# Mutli-Stepper-Driver_Rev_2_MRlocal.net
KiCad netlist of a schematic drawn in EAGLE
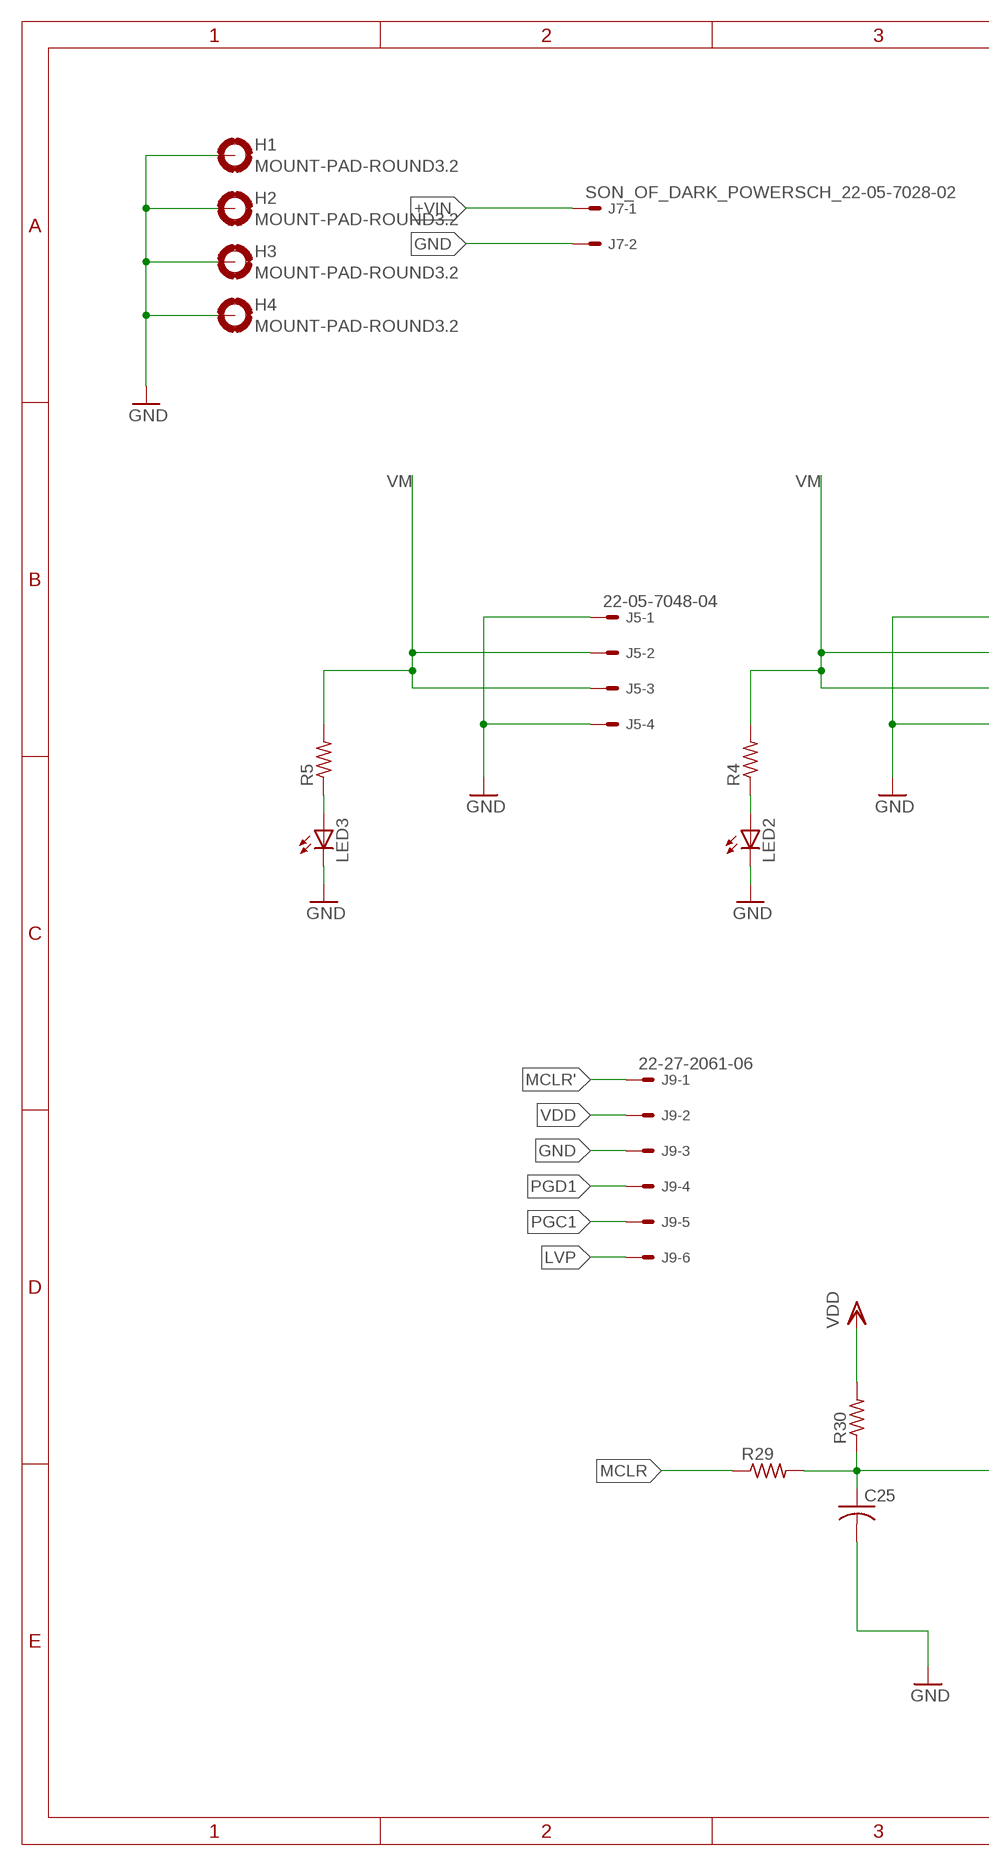
[diagram p0: schematic, sheet 1, part 1 of 2]
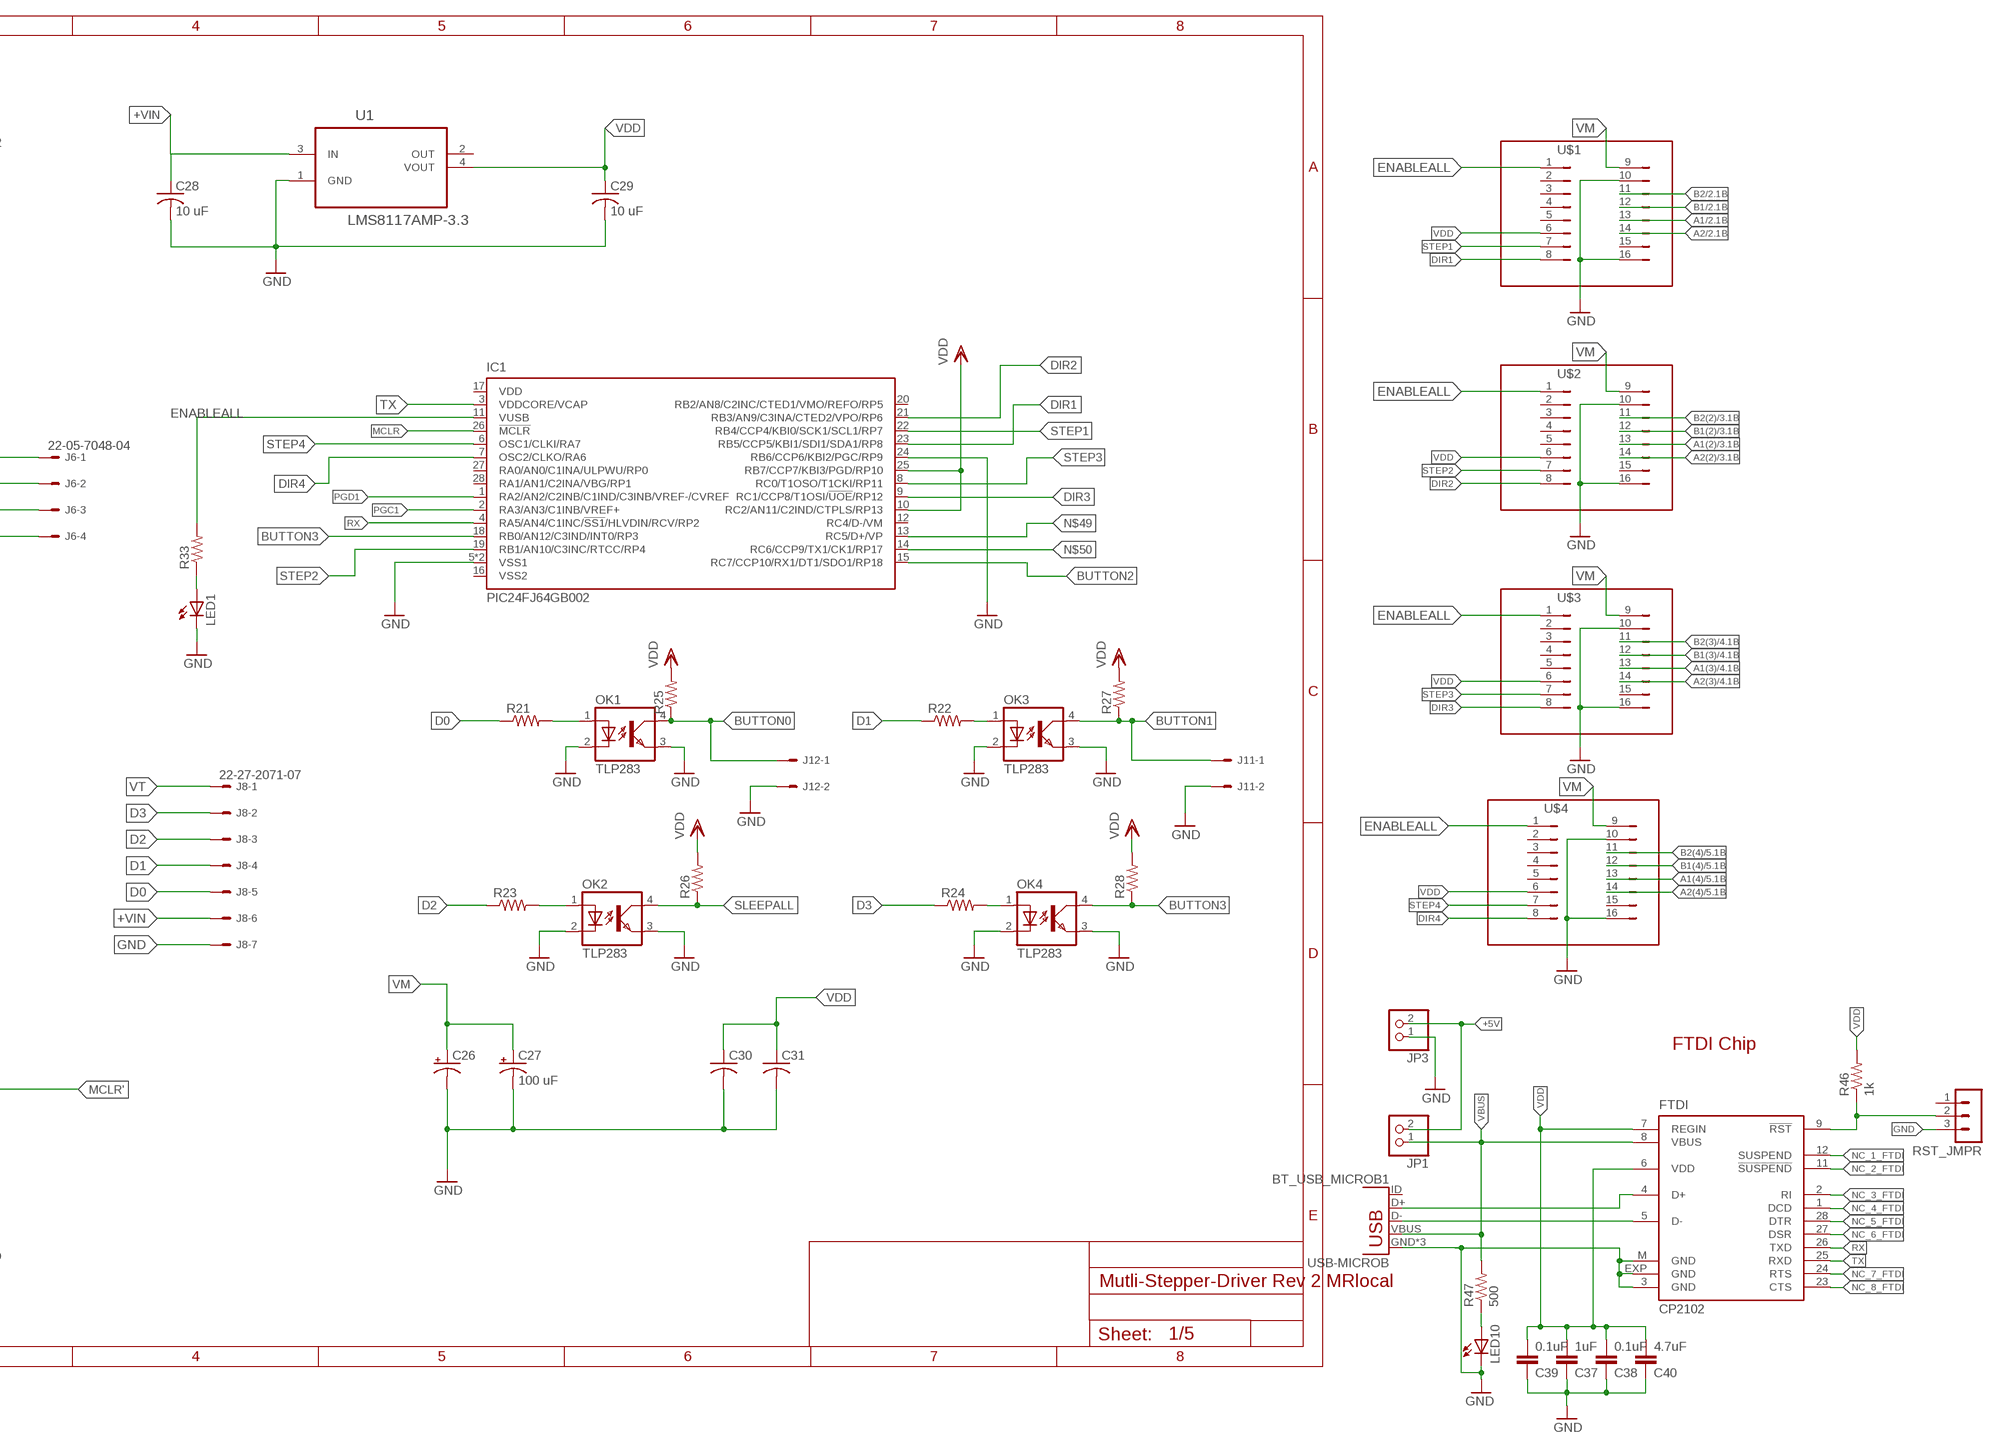
[diagram p1: schematic, sheet 1, part 2 of 2]
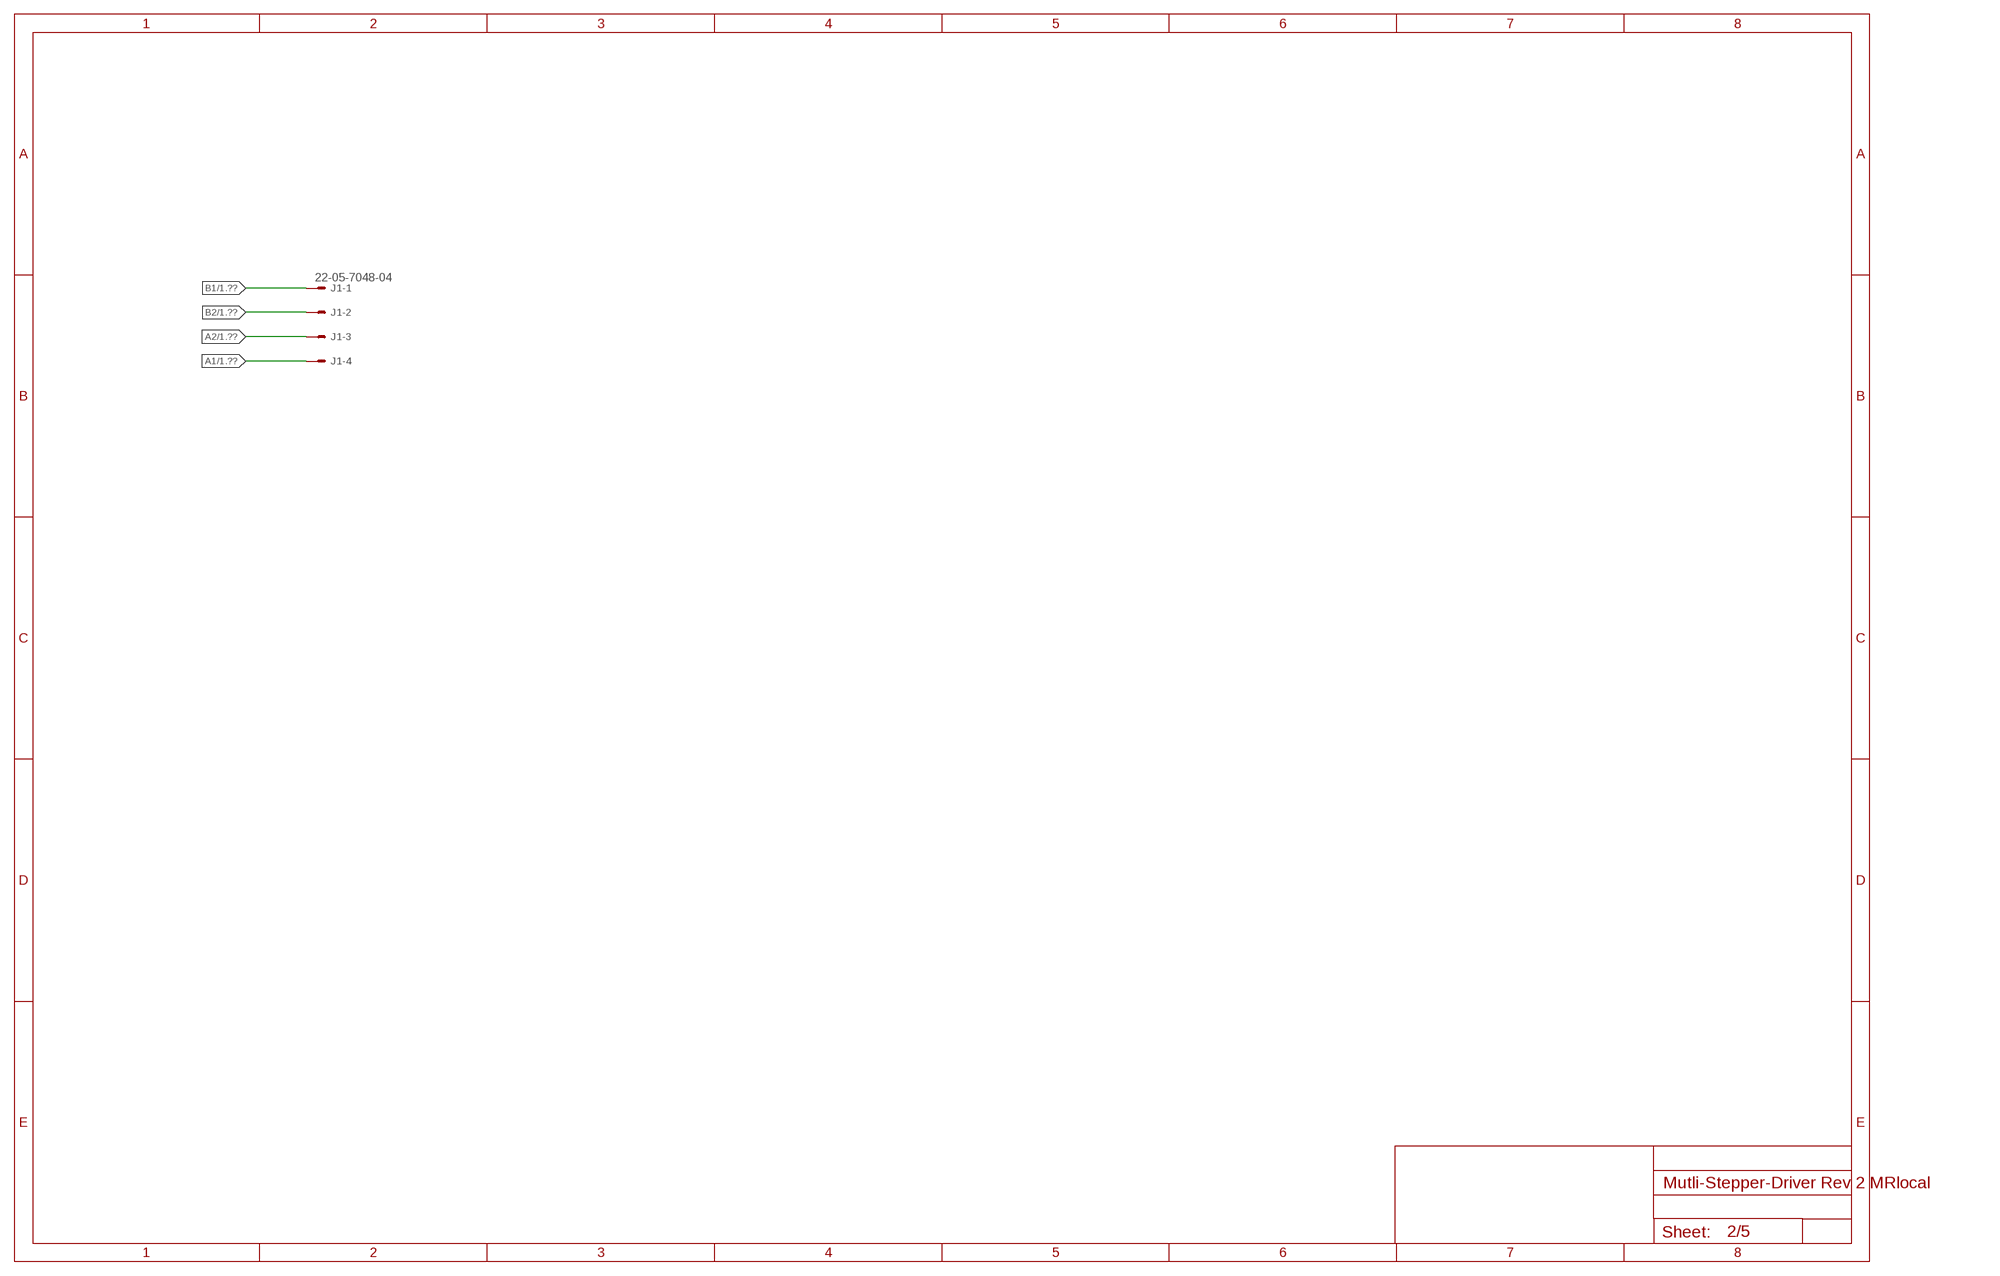
[diagram p2: schematic, sheet 2]
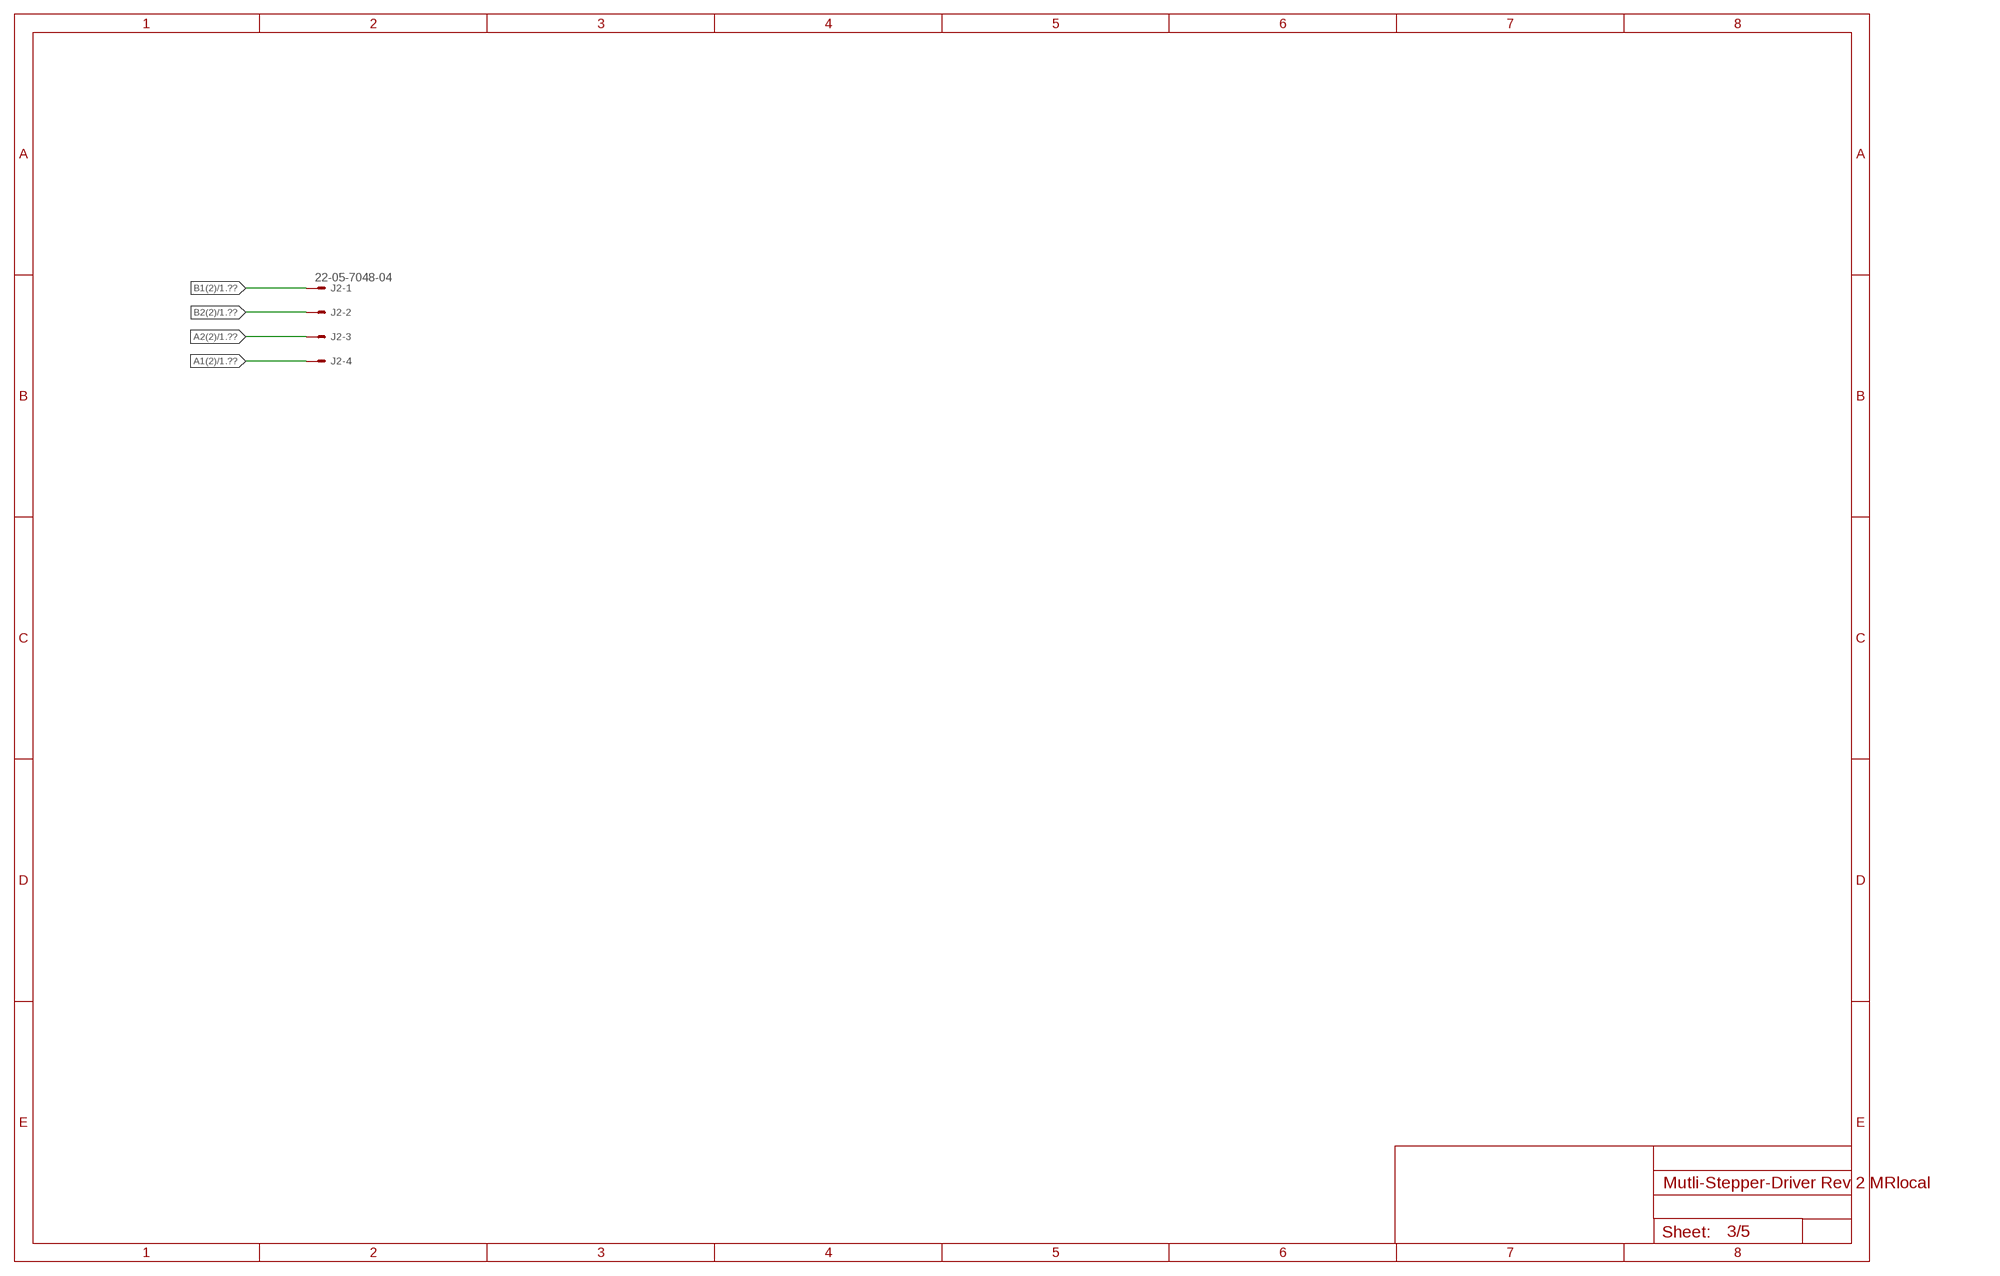
[diagram p3: schematic, sheet 3]
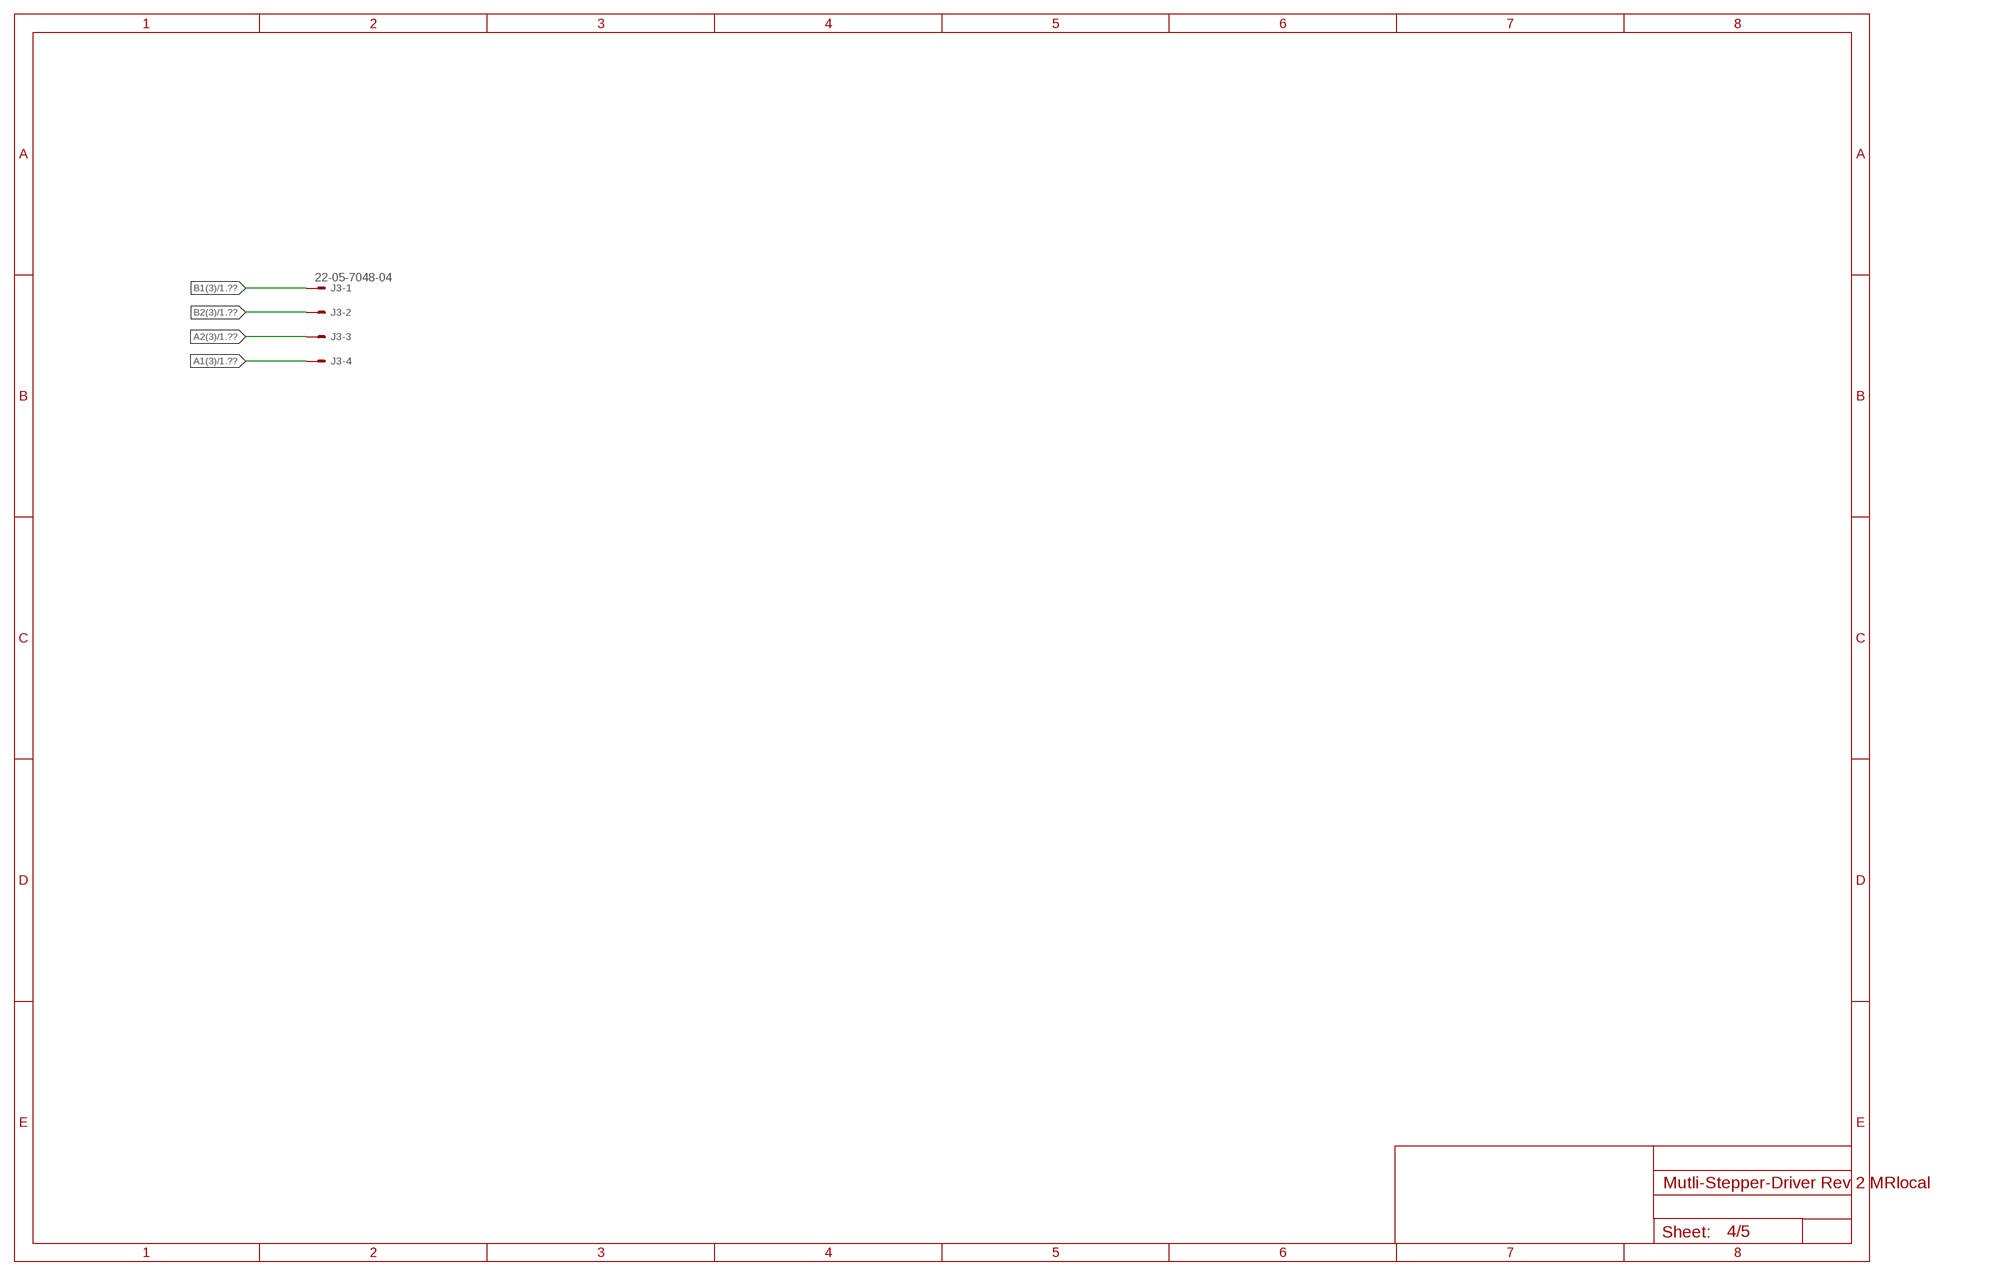
[diagram p4: schematic, sheet 4]
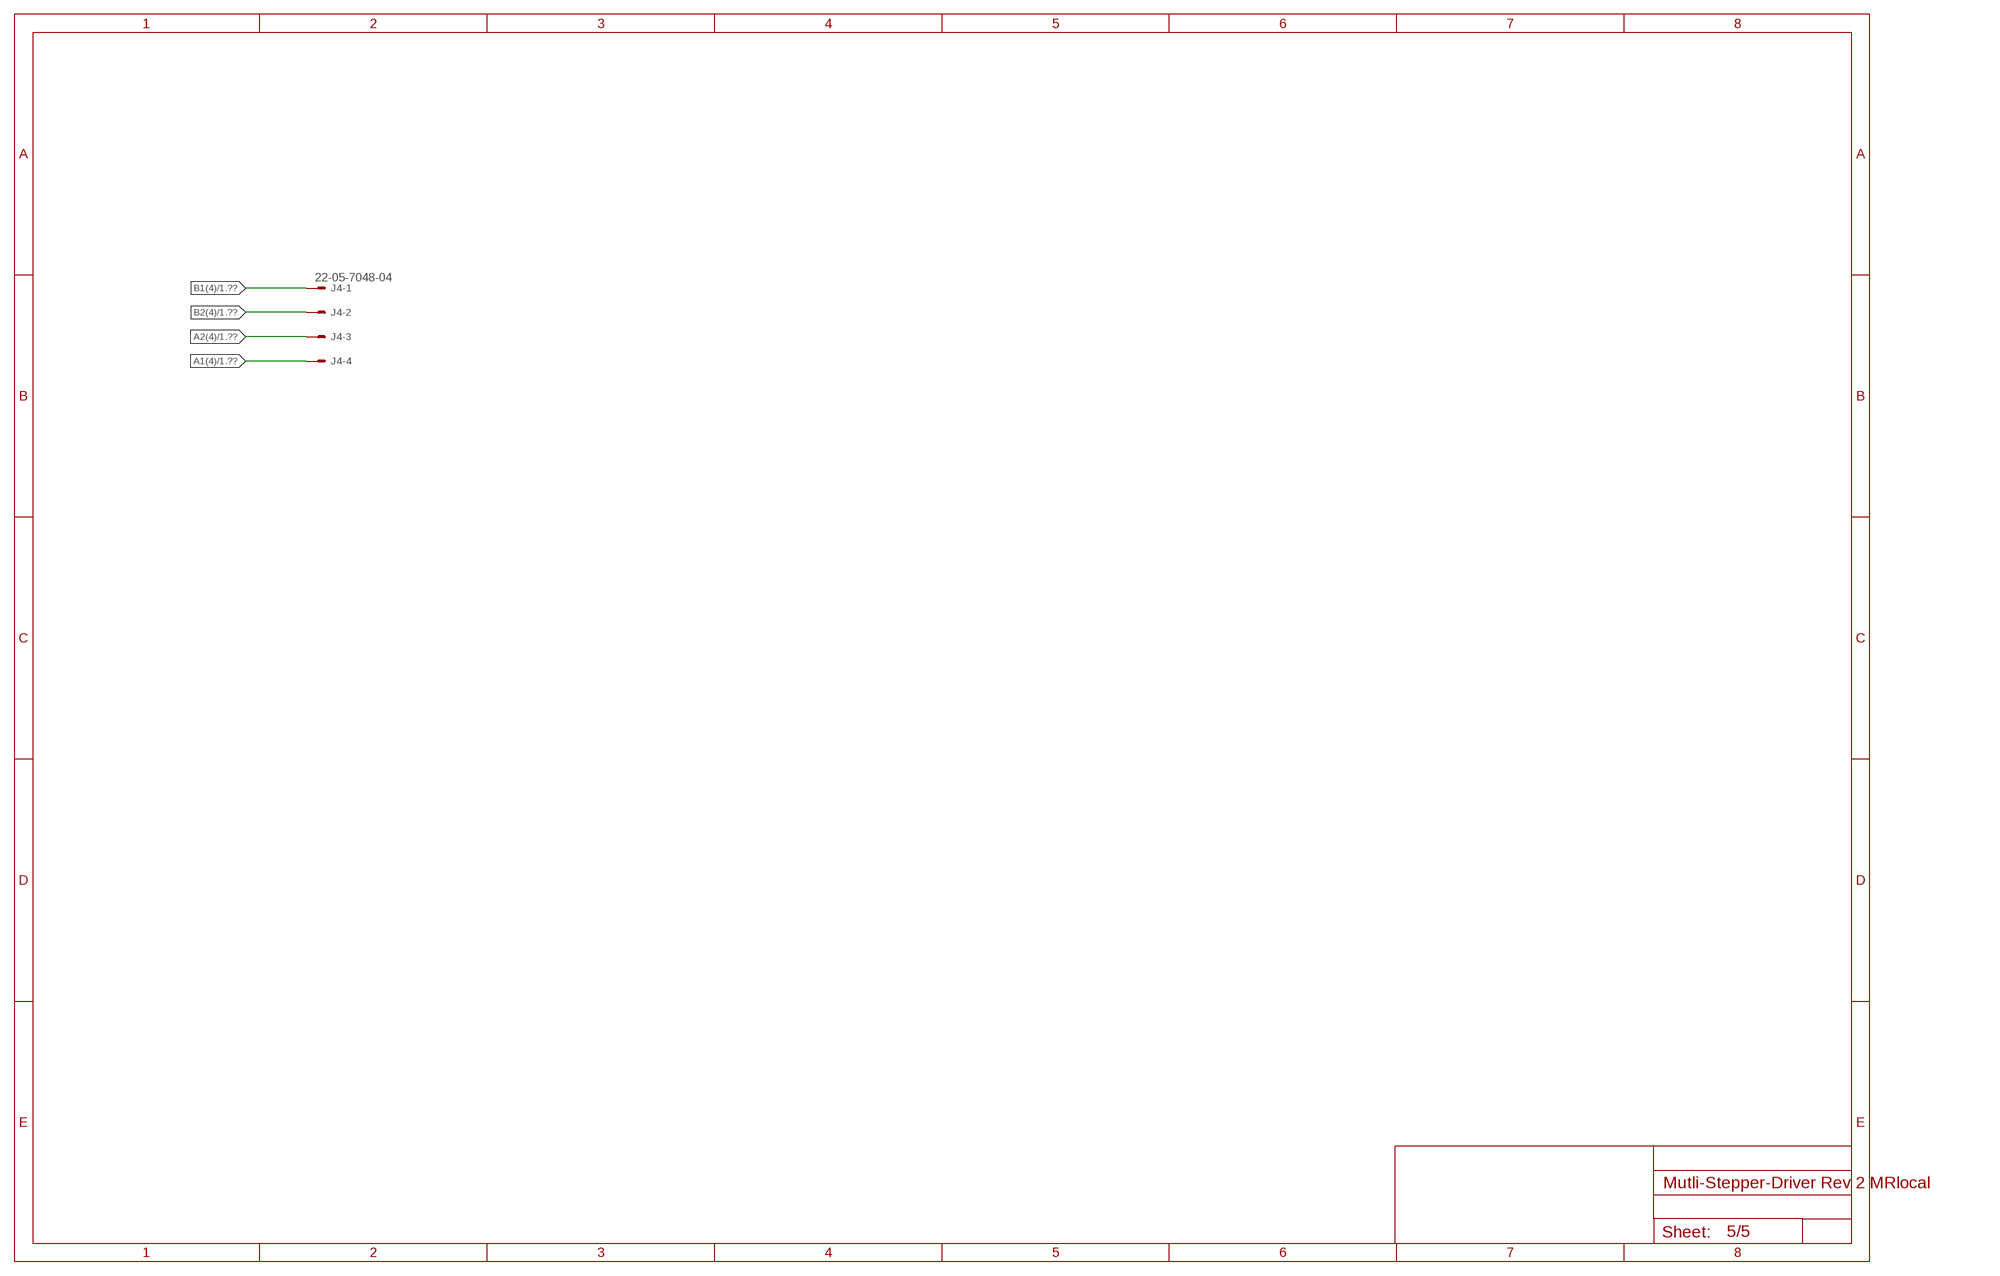
[diagram p5: schematic, sheet 5]

(export (version "E")
  (design (tool "Eeschema 10.0.6"))
  (components
    (comp (ref "J2")
      (value "22-05-7048-04")
      (footprint "eagle-import:7395-04")
      (libsource (lib "eagle-import") (part "22-?-0405-7048"))
    )
    (comp (ref "J3")
      (value "22-05-7048-04")
      (footprint "eagle-import:7395-04")
      (libsource (lib "eagle-import") (part "22-?-0405-7048"))
    )
    (comp (ref "J1")
      (value "22-05-7048-04")
      (footprint "eagle-import:7395-04")
      (libsource (lib "eagle-import") (part "22-?-0405-7048"))
    )
    (comp (ref "BT_USB_MICROB1")
      (value "USB-MICROB")
      (footprint "eagle-import:USB-MICROB")
      (libsource (lib "eagle-import") (part "USB-MICROB"))
    )
    (comp (ref "C25")
      (value "C-USC0805")
      (footprint "eagle-import:C0805")
      (libsource (lib "eagle-import") (part "C-USC0805"))
    )
    (comp (ref "C26")
      (value "CPOL-USCT7343")
      (footprint "eagle-import:CT7343")
      (libsource (lib "eagle-import") (part "CPOL-USCT7343"))
    )
    (comp (ref "C27")
      (value "100 uF")
      (footprint "eagle-import:CT7343")
      (libsource (lib "eagle-import") (part "CPOL-USCT7343"))
    )
    (comp (ref "C28")
      (value "10 uF")
      (footprint "eagle-import:C3216")
      (libsource (lib "eagle-import") (part "C-USC3216"))
    )
    (comp (ref "C29")
      (value "10 uF")
      (footprint "eagle-import:C3216")
      (libsource (lib "eagle-import") (part "C-USC3216"))
    )
    (comp (ref "C30")
      (value "C-USC0805")
      (footprint "eagle-import:C0805")
      (libsource (lib "eagle-import") (part "C-USC0805"))
    )
    (comp (ref "C31")
      (value "C-USC0805")
      (footprint "eagle-import:C0805")
      (libsource (lib "eagle-import") (part "C-USC0805"))
    )
    (comp (ref "C37")
      (value "1uF")
      (footprint "eagle-import:C0805")
      (libsource (lib "eagle-import") (part "C-EUC0805"))
    )
    (comp (ref "C38")
      (value "0.1uF")
      (footprint "eagle-import:C0805")
      (libsource (lib "eagle-import") (part "C-EUC0805"))
    )
    (comp (ref "C39")
      (value "0.1uF")
      (footprint "eagle-import:C0805")
      (libsource (lib "eagle-import") (part "C-EUC0805"))
    )
    (comp (ref "C40")
      (value "4.7uF")
      (footprint "eagle-import:C0805")
      (libsource (lib "eagle-import") (part "C-EUC0805"))
    )
    (comp (ref "FTDI")
      (value "CP2102")
      (footprint "eagle-import:MLP28")
      (fields (field (name "MF") "FARNELL") (field (name "MPN") "CP2102-GM"))
      (libsource (lib "eagle-import") (part "CP2102"))
    )
    (comp (ref "H1")
      (value "MOUNT-PAD-ROUND3.2")
      (footprint "eagle-import:3,2-PAD")
      (libsource (lib "eagle-import") (part "MOUNT-PAD-ROUND3.2"))
    )
    (comp (ref "H2")
      (value "MOUNT-PAD-ROUND3.2")
      (footprint "eagle-import:3,2-PAD")
      (libsource (lib "eagle-import") (part "MOUNT-PAD-ROUND3.2"))
    )
    (comp (ref "H3")
      (value "MOUNT-PAD-ROUND3.2")
      (footprint "eagle-import:3,2-PAD")
      (libsource (lib "eagle-import") (part "MOUNT-PAD-ROUND3.2"))
    )
    (comp (ref "H4")
      (value "MOUNT-PAD-ROUND3.2")
      (footprint "eagle-import:3,2-PAD")
      (libsource (lib "eagle-import") (part "MOUNT-PAD-ROUND3.2"))
    )
    (comp (ref "IC1")
      (value "PIC24FJ64GB002")
      (footprint "eagle-import:MICROCHIP_QFN28-ML_6X6MM")
      (libsource (lib "eagle-import") (part "MICROCHIP_PIC18F2J53ML"))
    )
    (comp (ref "J5")
      (value "22-05-7048-04")
      (footprint "eagle-import:7395-04")
      (libsource (lib "eagle-import") (part "22-?-0405-7048"))
    )
    (comp (ref "J6")
      (value "22-05-7048-04")
      (footprint "eagle-import:7395-04")
      (libsource (lib "eagle-import") (part "22-?-0405-7048"))
    )
    (comp (ref "J7")
      (value "SON_OF_DARK_POWERSCH_22-05-7028-02")
      (footprint "eagle-import:SON_OF_DARK_POWERSCH_7395-02")
      (libsource (lib "eagle-import") (part "SON_OF_DARK_POWERSCH_22-?-0205-7028"))
    )
    (comp (ref "J8")
      (value "22-27-2071-07")
      (footprint "eagle-import:6410-07")
      (libsource (lib "eagle-import") (part "22-?-0727-2071"))
    )
    (comp (ref "J9")
      (value "22-27-2061-06")
      (footprint "eagle-import:6410-06")
      (libsource (lib "eagle-import") (part "22-?-0627-2061"))
    )
    (comp (ref "J11")
      (value "SON_OF_DARK_POWERSCH_22-05-7028-02")
      (footprint "eagle-import:SON_OF_DARK_POWERSCH_7395-02")
      (libsource (lib "eagle-import") (part "SON_OF_DARK_POWERSCH_22-?-0205-7028"))
    )
    (comp (ref "J12")
      (value "SON_OF_DARK_POWERSCH_22-05-7028-02")
      (footprint "eagle-import:SON_OF_DARK_POWERSCH_7395-02")
      (libsource (lib "eagle-import") (part "SON_OF_DARK_POWERSCH_22-?-0205-7028"))
    )
    (comp (ref "JP1")
      (value "PINHD-1X2")
      (footprint "eagle-import:1X02")
      (libsource (lib "eagle-import") (part "PINHD-1X2"))
    )
    (comp (ref "JP3")
      (value "PINHD-1X2")
      (footprint "eagle-import:1X02")
      (libsource (lib "eagle-import") (part "PINHD-1X2"))
    )
    (comp (ref "LED1")
      (value "LEDCHIPLED_0805")
      (footprint "eagle-import:CHIPLED_0805")
      (libsource (lib "eagle-import") (part "led_LEDCHIPLED_0805"))
    )
    (comp (ref "LED2")
      (value "LEDCHIPLED_0805")
      (footprint "eagle-import:CHIPLED_0805")
      (libsource (lib "eagle-import") (part "led_LEDCHIPLED_0805"))
    )
    (comp (ref "LED3")
      (value "LEDCHIPLED_0805")
      (footprint "eagle-import:CHIPLED_0805")
      (libsource (lib "eagle-import") (part "led_LEDCHIPLED_0805"))
    )
    (comp (ref "LED10")
      (value "LEDSML0603")
      (footprint "eagle-import:SML0603")
      (libsource (lib "eagle-import") (part "LEDSML0603"))
    )
    (comp (ref "OK1")
      (value "TLP283")
      (footprint "eagle-import:MINI-FLAT-4")
      (libsource (lib "eagle-import") (part "TLP283"))
    )
    (comp (ref "OK2")
      (value "TLP283")
      (footprint "eagle-import:MINI-FLAT-4")
      (libsource (lib "eagle-import") (part "TLP283"))
    )
    (comp (ref "OK3")
      (value "TLP283")
      (footprint "eagle-import:MINI-FLAT-4")
      (libsource (lib "eagle-import") (part "TLP283"))
    )
    (comp (ref "OK4")
      (value "TLP283")
      (footprint "eagle-import:MINI-FLAT-4")
      (libsource (lib "eagle-import") (part "TLP283"))
    )
    (comp (ref "R4")
      (value "R-US_R0805")
      (footprint "eagle-import:R0805")
      (libsource (lib "eagle-import") (part "R-US_R0805"))
    )
    (comp (ref "R5")
      (value "R-US_R0805")
      (footprint "eagle-import:R0805")
      (libsource (lib "eagle-import") (part "R-US_R0805"))
    )
    (comp (ref "R21")
      (value "R-US_R0805")
      (footprint "eagle-import:R0805")
      (libsource (lib "eagle-import") (part "R-US_R0805"))
    )
    (comp (ref "R22")
      (value "R-US_R0805")
      (footprint "eagle-import:R0805")
      (libsource (lib "eagle-import") (part "R-US_R0805"))
    )
    (comp (ref "R23")
      (value "R-US_R0805")
      (footprint "eagle-import:R0805")
      (libsource (lib "eagle-import") (part "R-US_R0805"))
    )
    (comp (ref "R24")
      (value "R-US_R0805")
      (footprint "eagle-import:R0805")
      (libsource (lib "eagle-import") (part "R-US_R0805"))
    )
    (comp (ref "R25")
      (value "R-US_R0805")
      (footprint "eagle-import:R0805")
      (libsource (lib "eagle-import") (part "R-US_R0805"))
    )
    (comp (ref "R26")
      (value "R-US_R0805")
      (footprint "eagle-import:R0805")
      (libsource (lib "eagle-import") (part "R-US_R0805"))
    )
    (comp (ref "R27")
      (value "R-US_R0805")
      (footprint "eagle-import:R0805")
      (libsource (lib "eagle-import") (part "R-US_R0805"))
    )
    (comp (ref "R28")
      (value "R-US_R0805")
      (footprint "eagle-import:R0805")
      (libsource (lib "eagle-import") (part "R-US_R0805"))
    )
    (comp (ref "R29")
      (value "R-US_R0805")
      (footprint "eagle-import:R0805")
      (libsource (lib "eagle-import") (part "R-US_R0805"))
    )
    (comp (ref "R30")
      (value "R-US_R0805")
      (footprint "eagle-import:R0805")
      (libsource (lib "eagle-import") (part "R-US_R0805"))
    )
    (comp (ref "R33")
      (value "R-US_R0805")
      (footprint "eagle-import:R0805")
      (libsource (lib "eagle-import") (part "R-US_R0805"))
    )
    (comp (ref "R46")
      (value "1k")
      (footprint "eagle-import:R0805")
      (libsource (lib "eagle-import") (part "resistor_R-US_R0805"))
    )
    (comp (ref "R47")
      (value "500")
      (footprint "eagle-import:R0805")
      (libsource (lib "eagle-import") (part "resistor_R-US_R0805"))
    )
    (comp (ref "RST_JMPR")
      (value "MA03-1")
      (footprint "eagle-import:MA03-1")
      (libsource (lib "eagle-import") (part "MA03-1"))
    )
    (comp (ref "U$1")
      (value "DRIVER")
      (footprint "eagle-import:6410-08")
      (libsource (lib "eagle-import") (part "DRIVER"))
    )
    (comp (ref "U$2")
      (value "DRIVER")
      (footprint "eagle-import:6410-08")
      (libsource (lib "eagle-import") (part "DRIVER"))
    )
    (comp (ref "U$3")
      (value "DRIVER")
      (footprint "eagle-import:6410-08")
      (libsource (lib "eagle-import") (part "DRIVER"))
    )
    (comp (ref "U$4")
      (value "DRIVER")
      (footprint "eagle-import:6410-08")
      (libsource (lib "eagle-import") (part "DRIVER"))
    )
    (comp (ref "U1")
      (value "LMS8117AMP-3.3")
      (footprint "eagle-import:NSC-LMS8117AMP_SOT230P696X180-4N")
      (libsource (lib "eagle-import") (part "NSC-LMS8117AMP_LMS8117AMP-3.3"))
    )
    (comp (ref "J4")
      (value "22-05-7048-04")
      (footprint "eagle-import:7395-04")
      (libsource (lib "eagle-import") (part "22-?-0405-7048"))
    )
  )
  (nets
    (net (code "1") (name "+5V") (class "Default")
      (node (ref "JP1") (pin "2") (pinfunction "2_2") (pintype "passive"))
      (node (ref "JP3") (pin "2") (pinfunction "2_2") (pintype "passive"))
    )
    (net (code "2") (name "+VIN") (class "Default")
      (node (ref "C28") (pin "1") (pinfunction "1_1") (pintype "passive"))
      (node (ref "J7") (pin "1") (pinfunction "S_1") (pintype "passive"))
      (node (ref "J8") (pin "6") (pinfunction "S_6") (pintype "passive"))
      (node (ref "U1") (pin "3") (pinfunction "IN_3") (pintype "power_in"))
    )
    (net (code "3") (name "A1") (class "Default")
      (node (ref "J1") (pin "4") (pinfunction "S_4") (pintype "passive"))
      (node (ref "U$1") (pin "13") (pinfunction "13_13") (pintype "passive"))
    )
    (net (code "4") (name "A1(2)") (class "Default")
      (node (ref "J2") (pin "4") (pinfunction "S_4") (pintype "passive"))
      (node (ref "U$2") (pin "13") (pinfunction "13_13") (pintype "passive"))
    )
    (net (code "5") (name "A1(3)") (class "Default")
      (node (ref "J3") (pin "4") (pinfunction "S_4") (pintype "passive"))
      (node (ref "U$3") (pin "13") (pinfunction "13_13") (pintype "passive"))
    )
    (net (code "6") (name "A1(4)") (class "Default")
      (node (ref "J4") (pin "4") (pinfunction "S_4") (pintype "passive"))
      (node (ref "U$4") (pin "13") (pinfunction "13_13") (pintype "passive"))
    )
    (net (code "7") (name "A2") (class "Default")
      (node (ref "J1") (pin "3") (pinfunction "S_3") (pintype "passive"))
      (node (ref "U$1") (pin "14") (pinfunction "14_14") (pintype "passive"))
    )
    (net (code "8") (name "A2(2)") (class "Default")
      (node (ref "J2") (pin "3") (pinfunction "S_3") (pintype "passive"))
      (node (ref "U$2") (pin "14") (pinfunction "14_14") (pintype "passive"))
    )
    (net (code "9") (name "A2(3)") (class "Default")
      (node (ref "J3") (pin "3") (pinfunction "S_3") (pintype "passive"))
      (node (ref "U$3") (pin "14") (pinfunction "14_14") (pintype "passive"))
    )
    (net (code "10") (name "A2(4)") (class "Default")
      (node (ref "J4") (pin "3") (pinfunction "S_3") (pintype "passive"))
      (node (ref "U$4") (pin "14") (pinfunction "14_14") (pintype "passive"))
    )
    (net (code "11") (name "B1") (class "Default")
      (node (ref "J1") (pin "1") (pinfunction "S_1") (pintype "passive"))
      (node (ref "U$1") (pin "12") (pinfunction "12_12") (pintype "passive"))
    )
    (net (code "12") (name "B1(2)") (class "Default")
      (node (ref "J2") (pin "1") (pinfunction "S_1") (pintype "passive"))
      (node (ref "U$2") (pin "12") (pinfunction "12_12") (pintype "passive"))
    )
    (net (code "13") (name "B1(3)") (class "Default")
      (node (ref "J3") (pin "1") (pinfunction "S_1") (pintype "passive"))
      (node (ref "U$3") (pin "12") (pinfunction "12_12") (pintype "passive"))
    )
    (net (code "14") (name "B1(4)") (class "Default")
      (node (ref "J4") (pin "1") (pinfunction "S_1") (pintype "passive"))
      (node (ref "U$4") (pin "12") (pinfunction "12_12") (pintype "passive"))
    )
    (net (code "15") (name "B2") (class "Default")
      (node (ref "J1") (pin "2") (pinfunction "S_2") (pintype "passive"))
      (node (ref "U$1") (pin "11") (pinfunction "11_11") (pintype "passive"))
    )
    (net (code "16") (name "B2(2)") (class "Default")
      (node (ref "J2") (pin "2") (pinfunction "S_2") (pintype "passive"))
      (node (ref "U$2") (pin "11") (pinfunction "11_11") (pintype "passive"))
    )
    (net (code "17") (name "B2(3)") (class "Default")
      (node (ref "J3") (pin "2") (pinfunction "S_2") (pintype "passive"))
      (node (ref "U$3") (pin "11") (pinfunction "11_11") (pintype "passive"))
    )
    (net (code "18") (name "B2(4)") (class "Default")
      (node (ref "J4") (pin "2") (pinfunction "S_2") (pintype "passive"))
      (node (ref "U$4") (pin "11") (pinfunction "11_11") (pintype "passive"))
    )
    (net (code "19") (name "BUTTON0") (class "Default")
      (node (ref "J12") (pin "1") (pinfunction "S_1") (pintype "passive"))
      (node (ref "OK1") (pin "4") (pinfunction "COL_4") (pintype "passive"))
      (node (ref "R25") (pin "1") (pinfunction "1_1") (pintype "passive"))
    )
    (net (code "20") (name "BUTTON1") (class "Default")
      (node (ref "J11") (pin "1") (pinfunction "S_1") (pintype "passive"))
      (node (ref "OK3") (pin "4") (pinfunction "COL_4") (pintype "passive"))
      (node (ref "R27") (pin "1") (pinfunction "1_1") (pintype "passive"))
    )
    (net (code "21") (name "BUTTON2") (class "Default")
      (node (ref "IC1") (pin "15") (pinfunction "RC7/CCP10/RX1/DT1/SDO1/RP18_15") (pintype "bidirectional"))
    )
    (net (code "22") (name "BUTTON3") (class "Default")
      (node (ref "IC1") (pin "18") (pinfunction "RB0/AN12/C3IND/INT0/RP3_18") (pintype "bidirectional"))
      (node (ref "OK4") (pin "4") (pinfunction "COL_4") (pintype "passive"))
      (node (ref "R28") (pin "1") (pinfunction "1_1") (pintype "passive"))
    )
    (net (code "23") (name "D0") (class "Default")
      (node (ref "J8") (pin "5") (pinfunction "S_5") (pintype "passive"))
      (node (ref "R21") (pin "1") (pinfunction "1_1") (pintype "passive"))
    )
    (net (code "24") (name "D1") (class "Default")
      (node (ref "J8") (pin "4") (pinfunction "S_4") (pintype "passive"))
      (node (ref "R22") (pin "1") (pinfunction "1_1") (pintype "passive"))
    )
    (net (code "25") (name "D2") (class "Default")
      (node (ref "J8") (pin "3") (pinfunction "S_3") (pintype "passive"))
      (node (ref "R23") (pin "1") (pinfunction "1_1") (pintype "passive"))
    )
    (net (code "26") (name "D3") (class "Default")
      (node (ref "J8") (pin "2") (pinfunction "S_2") (pintype "passive"))
      (node (ref "R24") (pin "1") (pinfunction "1_1") (pintype "passive"))
    )
    (net (code "27") (name "DIR1") (class "Default")
      (node (ref "IC1") (pin "23") (pinfunction "RB5/CCP5/KBI1/SDI1/SDA1/RP8_23") (pintype "bidirectional"))
      (node (ref "U$1") (pin "8") (pinfunction "8_8") (pintype "passive"))
    )
    (net (code "28") (name "DIR2") (class "Default")
      (node (ref "IC1") (pin "21") (pinfunction "RB3/AN9/C3INA/CTED2/VPO/RP6_21") (pintype "bidirectional"))
      (node (ref "U$2") (pin "8") (pinfunction "8_8") (pintype "passive"))
    )
    (net (code "29") (name "DIR3") (class "Default")
      (node (ref "IC1") (pin "9") (pinfunction "RC1/CCP8/T1OSI/~{UOE}/RP12_9") (pintype "bidirectional"))
      (node (ref "U$3") (pin "8") (pinfunction "8_8") (pintype "passive"))
    )
    (net (code "30") (name "DIR4") (class "Default")
      (node (ref "IC1") (pin "7") (pinfunction "OSC2/CLKO/RA6_7") (pintype "bidirectional"))
      (node (ref "U$4") (pin "8") (pinfunction "8_8") (pintype "passive"))
    )
    (net (code "31") (name "ENABLEALL") (class "Default")
      (node (ref "IC1") (pin "11") (pinfunction "VUSB_11") (pintype "input"))
      (node (ref "R33") (pin "2") (pinfunction "2_2") (pintype "passive"))
      (node (ref "U$1") (pin "1") (pinfunction "1_1") (pintype "passive"))
      (node (ref "U$2") (pin "1") (pinfunction "1_1") (pintype "passive"))
      (node (ref "U$3") (pin "1") (pinfunction "1_1") (pintype "passive"))
      (node (ref "U$4") (pin "1") (pinfunction "1_1") (pintype "passive"))
    )
    (net (code "32") (name "GND") (class "Default")
      (node (ref "BT_USB_MICROB1") (pin "GND") (pinfunction "GND_GND") (pintype "bidirectional"))
      (node (ref "BT_USB_MICROB1") (pin "MT1") (pinfunction "GND_MT1") (pintype "bidirectional"))
      (node (ref "BT_USB_MICROB1") (pin "MT2") (pinfunction "GND_MT2") (pintype "bidirectional"))
      (node (ref "C25") (pin "2") (pinfunction "2_2") (pintype "passive"))
      (node (ref "C26") (pin "-") (pinfunction "-_-") (pintype "passive"))
      (node (ref "C27") (pin "-") (pinfunction "-_-") (pintype "passive"))
      (node (ref "C28") (pin "2") (pinfunction "2_2") (pintype "passive"))
      (node (ref "C29") (pin "2") (pinfunction "2_2") (pintype "passive"))
      (node (ref "C30") (pin "2") (pinfunction "2_2") (pintype "passive"))
      (node (ref "C31") (pin "2") (pinfunction "2_2") (pintype "passive"))
      (node (ref "C37") (pin "1") (pinfunction "1_1") (pintype "passive"))
      (node (ref "C38") (pin "1") (pinfunction "1_1") (pintype "passive"))
      (node (ref "C39") (pin "1") (pinfunction "1_1") (pintype "passive"))
      (node (ref "C40") (pin "1") (pinfunction "1_1") (pintype "passive"))
      (node (ref "FTDI") (pin "3") (pinfunction "GND_3") (pintype "power_in"))
      (node (ref "FTDI") (pin "EXP") (pinfunction "GND_EXP") (pintype "power_in"))
      (node (ref "FTDI") (pin "M") (pinfunction "GND_M") (pintype "power_in"))
      (node (ref "H1") (pin "B3,2") (pinfunction "MOUNT_B3,2") (pintype "passive"))
      (node (ref "H2") (pin "B3,2") (pinfunction "MOUNT_B3,2") (pintype "passive"))
      (node (ref "H3") (pin "B3,2") (pinfunction "MOUNT_B3,2") (pintype "passive"))
      (node (ref "H4") (pin "B3,2") (pinfunction "MOUNT_B3,2") (pintype "passive"))
      (node (ref "IC1") (pin "24") (pinfunction "RB6/CCP6/KBI2/PGC/RP9_24") (pintype "bidirectional"))
      (node (ref "IC1") (pin "5") (pinfunction "VSS1_5") (pintype "input"))
      (node (ref "IC1") (pin "EXP") (pinfunction "VSS1_EXP") (pintype "input"))
      (node (ref "J11") (pin "2") (pinfunction "S_2") (pintype "passive"))
      (node (ref "J12") (pin "2") (pinfunction "S_2") (pintype "passive"))
      (node (ref "J5") (pin "1") (pinfunction "S_1") (pintype "passive"))
      (node (ref "J5") (pin "4") (pinfunction "S_4") (pintype "passive"))
      (node (ref "J6") (pin "1") (pinfunction "S_1") (pintype "passive"))
      (node (ref "J6") (pin "4") (pinfunction "S_4") (pintype "passive"))
      (node (ref "J7") (pin "2") (pinfunction "S_2") (pintype "passive"))
      (node (ref "J8") (pin "7") (pinfunction "S_7") (pintype "passive"))
      (node (ref "J9") (pin "3") (pinfunction "S_3") (pintype "passive"))
      (node (ref "JP3") (pin "1") (pinfunction "1_1") (pintype "passive"))
      (node (ref "LED1") (pin "C") (pinfunction "C_C") (pintype "passive"))
      (node (ref "LED10") (pin "C") (pinfunction "C_C") (pintype "passive"))
      (node (ref "LED2") (pin "C") (pinfunction "C_C") (pintype "passive"))
      (node (ref "LED3") (pin "C") (pinfunction "C_C") (pintype "passive"))
      (node (ref "OK1") (pin "2") (pinfunction "C_2") (pintype "passive"))
      (node (ref "OK1") (pin "3") (pinfunction "EMIT_3") (pintype "passive"))
      (node (ref "OK2") (pin "2") (pinfunction "C_2") (pintype "passive"))
      (node (ref "OK2") (pin "3") (pinfunction "EMIT_3") (pintype "passive"))
      (node (ref "OK3") (pin "2") (pinfunction "C_2") (pintype "passive"))
      (node (ref "OK3") (pin "3") (pinfunction "EMIT_3") (pintype "passive"))
      (node (ref "OK4") (pin "2") (pinfunction "C_2") (pintype "passive"))
      (node (ref "OK4") (pin "3") (pinfunction "EMIT_3") (pintype "passive"))
      (node (ref "RST_JMPR") (pin "3") (pinfunction "3_3") (pintype "passive"))
      (node (ref "U$1") (pin "10") (pinfunction "10_10") (pintype "passive"))
      (node (ref "U$1") (pin "16") (pinfunction "16_16") (pintype "passive"))
      (node (ref "U$2") (pin "10") (pinfunction "10_10") (pintype "passive"))
      (node (ref "U$2") (pin "16") (pinfunction "16_16") (pintype "passive"))
      (node (ref "U$3") (pin "10") (pinfunction "10_10") (pintype "passive"))
      (node (ref "U$3") (pin "16") (pinfunction "16_16") (pintype "passive"))
      (node (ref "U$4") (pin "10") (pinfunction "10_10") (pintype "passive"))
      (node (ref "U$4") (pin "16") (pinfunction "16_16") (pintype "passive"))
      (node (ref "U1") (pin "1") (pinfunction "GND_1") (pintype "passive"))
    )
    (net (code "33") (name "LVP") (class "Default")
      (node (ref "J9") (pin "6") (pinfunction "S_6") (pintype "passive"))
    )
    (net (code "34") (name "MCLR") (class "Default")
      (node (ref "IC1") (pin "26") (pinfunction "~{MCLR}_26") (pintype "input"))
      (node (ref "R29") (pin "1") (pinfunction "1_1") (pintype "passive"))
    )
    (net (code "35") (name "MCLR'") (class "Default")
      (node (ref "C25") (pin "1") (pinfunction "1_1") (pintype "passive"))
      (node (ref "J9") (pin "1") (pinfunction "S_1") (pintype "passive"))
      (node (ref "R29") (pin "2") (pinfunction "2_2") (pintype "passive"))
      (node (ref "R30") (pin "1") (pinfunction "1_1") (pintype "passive"))
    )
    (net (code "36") (name "N$49") (class "Default")
      (node (ref "IC1") (pin "13") (pinfunction "RC5/D+/VP_13") (pintype "bidirectional"))
    )
    (net (code "37") (name "N$50") (class "Default")
      (node (ref "IC1") (pin "14") (pinfunction "RC6/CCP9/TX1/CK1/RP17_14") (pintype "bidirectional"))
    )
    (net (code "38") (name "NC_1_FTDI") (class "Default")
      (node (ref "FTDI") (pin "12") (pinfunction "SUSPEND_12") (pintype "output"))
    )
    (net (code "39") (name "NC_2_FTDI") (class "Default")
      (node (ref "FTDI") (pin "11") (pinfunction "~{SUSPEND}_11") (pintype "output"))
    )
    (net (code "40") (name "NC_3_FTDI") (class "Default")
      (node (ref "FTDI") (pin "2") (pinfunction "RI_2") (pintype "input"))
    )
    (net (code "41") (name "NC_4_FTDI") (class "Default")
      (node (ref "FTDI") (pin "1") (pinfunction "DCD_1") (pintype "input"))
    )
    (net (code "42") (name "NC_5_FTDI") (class "Default")
      (node (ref "FTDI") (pin "28") (pinfunction "DTR_28") (pintype "output"))
    )
    (net (code "43") (name "NC_6_FTDI") (class "Default")
      (node (ref "FTDI") (pin "27") (pinfunction "DSR_27") (pintype "input"))
    )
    (net (code "44") (name "NC_7_FTDI") (class "Default")
      (node (ref "FTDI") (pin "24") (pinfunction "RTS_24") (pintype "output"))
    )
    (net (code "45") (name "NC_8_FTDI") (class "Default")
      (node (ref "FTDI") (pin "23") (pinfunction "CTS_23") (pintype "input"))
    )
    (net (code "46") (name "Net-(FTDI-D+)") (class "Default")
      (node (ref "BT_USB_MICROB1") (pin "D+") (pinfunction "D+_D+") (pintype "bidirectional"))
      (node (ref "FTDI") (pin "4") (pinfunction "D+_4") (pintype "bidirectional"))
    )
    (net (code "47") (name "Net-(FTDI-D-)") (class "Default")
      (node (ref "BT_USB_MICROB1") (pin "D-") (pinfunction "D-_D-") (pintype "bidirectional"))
      (node (ref "FTDI") (pin "5") (pinfunction "D-_5") (pintype "bidirectional"))
    )
    (net (code "48") (name "Net-(FTDI-~{RST})") (class "Default")
      (node (ref "FTDI") (pin "9") (pinfunction "~{RST}_9") (pintype "bidirectional"))
      (node (ref "R46") (pin "1") (pinfunction "1_1") (pintype "passive"))
      (node (ref "RST_JMPR") (pin "2") (pinfunction "2_2") (pintype "passive"))
    )
    (net (code "49") (name "Net-(LED1-PadA)") (class "Default")
      (node (ref "LED1") (pin "A") (pinfunction "A_A") (pintype "passive"))
      (node (ref "R33") (pin "1") (pinfunction "1_1") (pintype "passive"))
    )
    (net (code "50") (name "Net-(LED2-PadA)") (class "Default")
      (node (ref "LED2") (pin "A") (pinfunction "A_A") (pintype "passive"))
      (node (ref "R4") (pin "1") (pinfunction "1_1") (pintype "passive"))
    )
    (net (code "51") (name "Net-(LED3-PadA)") (class "Default")
      (node (ref "LED3") (pin "A") (pinfunction "A_A") (pintype "passive"))
      (node (ref "R5") (pin "1") (pinfunction "1_1") (pintype "passive"))
    )
    (net (code "52") (name "Net-(LED10-PadA)") (class "Default")
      (node (ref "LED10") (pin "A") (pinfunction "A_A") (pintype "passive"))
      (node (ref "R47") (pin "1") (pinfunction "1_1") (pintype "passive"))
    )
    (net (code "53") (name "Net-(OK1-A)") (class "Default")
      (node (ref "OK1") (pin "1") (pinfunction "A_1") (pintype "passive"))
      (node (ref "R21") (pin "2") (pinfunction "2_2") (pintype "passive"))
    )
    (net (code "54") (name "Net-(OK2-A)") (class "Default")
      (node (ref "OK2") (pin "1") (pinfunction "A_1") (pintype "passive"))
      (node (ref "R23") (pin "2") (pinfunction "2_2") (pintype "passive"))
    )
    (net (code "55") (name "Net-(OK3-A)") (class "Default")
      (node (ref "OK3") (pin "1") (pinfunction "A_1") (pintype "passive"))
      (node (ref "R22") (pin "2") (pinfunction "2_2") (pintype "passive"))
    )
    (net (code "56") (name "Net-(OK4-A)") (class "Default")
      (node (ref "OK4") (pin "1") (pinfunction "A_1") (pintype "passive"))
      (node (ref "R24") (pin "2") (pinfunction "2_2") (pintype "passive"))
    )
    (net (code "57") (name "PGC1") (class "Default")
      (node (ref "IC1") (pin "2") (pinfunction "RA3/AN3/C1INB/VREF+_2") (pintype "bidirectional"))
      (node (ref "J9") (pin "5") (pinfunction "S_5") (pintype "passive"))
    )
    (net (code "58") (name "PGD1") (class "Default")
      (node (ref "IC1") (pin "1") (pinfunction "RA2/AN2/C2INB/C1IND/C3INB/VREF-/CVREF_1") (pintype "bidirectional"))
      (node (ref "J9") (pin "4") (pinfunction "S_4") (pintype "passive"))
    )
    (net (code "59") (name "RX") (class "Default")
      (node (ref "FTDI") (pin "26") (pinfunction "TXD_26") (pintype "output"))
      (node (ref "IC1") (pin "4") (pinfunction "RA5/AN4/C1INC/~{SS1}/HLVDIN/RCV/RP2_4") (pintype "bidirectional"))
    )
    (net (code "60") (name "SLEEPALL") (class "Default")
      (node (ref "OK2") (pin "4") (pinfunction "COL_4") (pintype "passive"))
      (node (ref "R26") (pin "1") (pinfunction "1_1") (pintype "passive"))
    )
    (net (code "61") (name "STEP1") (class "Default")
      (node (ref "IC1") (pin "22") (pinfunction "RB4/CCP4/KBI0/SCK1/SCL1/RP7_22") (pintype "bidirectional"))
      (node (ref "U$1") (pin "7") (pinfunction "7_7") (pintype "passive"))
    )
    (net (code "62") (name "STEP2") (class "Default")
      (node (ref "IC1") (pin "19") (pinfunction "RB1/AN10/C3INC/RTCC/RP4_19") (pintype "bidirectional"))
      (node (ref "U$2") (pin "7") (pinfunction "7_7") (pintype "passive"))
    )
    (net (code "63") (name "STEP3") (class "Default")
      (node (ref "IC1") (pin "8") (pinfunction "RC0/T1OSO/T1CKI/RP11_8") (pintype "bidirectional"))
      (node (ref "U$3") (pin "7") (pinfunction "7_7") (pintype "passive"))
    )
    (net (code "64") (name "STEP4") (class "Default")
      (node (ref "IC1") (pin "6") (pinfunction "OSC1/CLKI/RA7_6") (pintype "bidirectional"))
      (node (ref "U$4") (pin "7") (pinfunction "7_7") (pintype "passive"))
    )
    (net (code "65") (name "TX") (class "Default")
      (node (ref "FTDI") (pin "25") (pinfunction "RXD_25") (pintype "input"))
      (node (ref "IC1") (pin "3") (pinfunction "VDDCORE/VCAP_3") (pintype "input"))
    )
    (net (code "66") (name "VBUS") (class "Default")
      (node (ref "BT_USB_MICROB1") (pin "VBUS") (pinfunction "VBUS_VBUS") (pintype "bidirectional"))
      (node (ref "FTDI") (pin "8") (pinfunction "VBUS_8") (pintype "input"))
      (node (ref "JP1") (pin "1") (pinfunction "1_1") (pintype "passive"))
      (node (ref "R47") (pin "2") (pinfunction "2_2") (pintype "passive"))
    )
    (net (code "67") (name "VDD") (class "Default")
      (node (ref "C29") (pin "1") (pinfunction "1_1") (pintype "passive"))
      (node (ref "C30") (pin "1") (pinfunction "1_1") (pintype "passive"))
      (node (ref "C31") (pin "1") (pinfunction "1_1") (pintype "passive"))
      (node (ref "C37") (pin "2") (pinfunction "2_2") (pintype "passive"))
      (node (ref "C38") (pin "2") (pinfunction "2_2") (pintype "passive"))
      (node (ref "C39") (pin "2") (pinfunction "2_2") (pintype "passive"))
      (node (ref "C40") (pin "2") (pinfunction "2_2") (pintype "passive"))
      (node (ref "FTDI") (pin "6") (pinfunction "VDD_6") (pintype "power_in"))
      (node (ref "FTDI") (pin "7") (pinfunction "REGIN_7") (pintype "passive"))
      (node (ref "IC1") (pin "10") (pinfunction "RC2/AN11/C2IND/CTPLS/RP13_10") (pintype "bidirectional"))
      (node (ref "IC1") (pin "25") (pinfunction "RB7/CCP7/KBI3/PGD/RP10_25") (pintype "bidirectional"))
      (node (ref "J9") (pin "2") (pinfunction "S_2") (pintype "passive"))
      (node (ref "R25") (pin "2") (pinfunction "2_2") (pintype "passive"))
      (node (ref "R26") (pin "2") (pinfunction "2_2") (pintype "passive"))
      (node (ref "R27") (pin "2") (pinfunction "2_2") (pintype "passive"))
      (node (ref "R28") (pin "2") (pinfunction "2_2") (pintype "passive"))
      (node (ref "R30") (pin "2") (pinfunction "2_2") (pintype "passive"))
      (node (ref "R46") (pin "2") (pinfunction "2_2") (pintype "passive"))
      (node (ref "U$1") (pin "6") (pinfunction "6_6") (pintype "passive"))
      (node (ref "U$2") (pin "6") (pinfunction "6_6") (pintype "passive"))
      (node (ref "U$3") (pin "6") (pinfunction "6_6") (pintype "passive"))
      (node (ref "U$4") (pin "6") (pinfunction "6_6") (pintype "passive"))
      (node (ref "U1") (pin "4") (pinfunction "VOUT_4") (pintype "power_in"))
    )
    (net (code "68") (name "VM") (class "Default")
      (node (ref "C26") (pin "+") (pinfunction "+_+") (pintype "passive"))
      (node (ref "C27") (pin "+") (pinfunction "+_+") (pintype "passive"))
      (node (ref "J5") (pin "2") (pinfunction "S_2") (pintype "passive"))
      (node (ref "J5") (pin "3") (pinfunction "S_3") (pintype "passive"))
      (node (ref "J6") (pin "2") (pinfunction "S_2") (pintype "passive"))
      (node (ref "J6") (pin "3") (pinfunction "S_3") (pintype "passive"))
      (node (ref "R4") (pin "2") (pinfunction "2_2") (pintype "passive"))
      (node (ref "R5") (pin "2") (pinfunction "2_2") (pintype "passive"))
      (node (ref "U$1") (pin "9") (pinfunction "9_9") (pintype "passive"))
      (node (ref "U$2") (pin "9") (pinfunction "9_9") (pintype "passive"))
      (node (ref "U$3") (pin "9") (pinfunction "9_9") (pintype "passive"))
      (node (ref "U$4") (pin "9") (pinfunction "9_9") (pintype "passive"))
    )
    (net (code "69") (name "VT") (class "Default")
      (node (ref "J8") (pin "1") (pinfunction "S_1") (pintype "passive"))
    )
    (net (code "70") (name "unconnected-(BT_USB_MICROB1-PadID)") (class "Default")
      (node (ref "BT_USB_MICROB1") (pin "ID") (pinfunction "ID_ID") (pintype "bidirectional"))
    )
    (net (code "71") (name "unconnected-(IC1-RA0{slash}AN0{slash}C1INA{slash}ULPWU{slash}RP0-Pad27)") (class "Default")
      (node (ref "IC1") (pin "27") (pinfunction "RA0/AN0/C1INA/ULPWU/RP0_27") (pintype "bidirectional"))
    )
    (net (code "72") (name "unconnected-(IC1-RA1{slash}AN1{slash}C2INA{slash}VBG{slash}RP1-Pad28)") (class "Default")
      (node (ref "IC1") (pin "28") (pinfunction "RA1/AN1/C2INA/VBG/RP1_28") (pintype "bidirectional"))
    )
    (net (code "73") (name "unconnected-(IC1-RB2{slash}AN8{slash}C2INC{slash}CTED1{slash}VMO{slash}REFO{slash}RP5-Pad20)") (class "Default")
      (node (ref "IC1") (pin "20") (pinfunction "RB2/AN8/C2INC/CTED1/VMO/REFO/RP5_20") (pintype "bidirectional"))
    )
    (net (code "74") (name "unconnected-(IC1-RC4{slash}D-{slash}VM-Pad12)") (class "Default")
      (node (ref "IC1") (pin "12") (pinfunction "RC4/D-/VM_12") (pintype "bidirectional"))
    )
    (net (code "75") (name "unconnected-(IC1-VDD-Pad17)") (class "Default")
      (node (ref "IC1") (pin "17") (pinfunction "VDD_17") (pintype "input"))
    )
    (net (code "76") (name "unconnected-(IC1-VSS2-Pad16)") (class "Default")
      (node (ref "IC1") (pin "16") (pinfunction "VSS2_16") (pintype "input"))
    )
    (net (code "77") (name "unconnected-(RST_JMPR-Pad1)") (class "Default")
      (node (ref "RST_JMPR") (pin "1") (pinfunction "1_1") (pintype "passive"))
    )
    (net (code "78") (name "unconnected-(U$1-Pad2)") (class "Default")
      (node (ref "U$1") (pin "2") (pinfunction "2_2") (pintype "passive"))
    )
    (net (code "79") (name "unconnected-(U$1-Pad3)") (class "Default")
      (node (ref "U$1") (pin "3") (pinfunction "3_3") (pintype "passive"))
    )
    (net (code "80") (name "unconnected-(U$1-Pad4)") (class "Default")
      (node (ref "U$1") (pin "4") (pinfunction "4_4") (pintype "passive"))
    )
    (net (code "81") (name "unconnected-(U$1-Pad5)") (class "Default")
      (node (ref "U$1") (pin "5") (pinfunction "5_5") (pintype "passive"))
    )
    (net (code "82") (name "unconnected-(U$1-Pad15)") (class "Default")
      (node (ref "U$1") (pin "15") (pinfunction "15_15") (pintype "passive"))
    )
    (net (code "83") (name "unconnected-(U$2-Pad2)") (class "Default")
      (node (ref "U$2") (pin "2") (pinfunction "2_2") (pintype "passive"))
    )
    (net (code "84") (name "unconnected-(U$2-Pad3)") (class "Default")
      (node (ref "U$2") (pin "3") (pinfunction "3_3") (pintype "passive"))
    )
    (net (code "85") (name "unconnected-(U$2-Pad4)") (class "Default")
      (node (ref "U$2") (pin "4") (pinfunction "4_4") (pintype "passive"))
    )
    (net (code "86") (name "unconnected-(U$2-Pad5)") (class "Default")
      (node (ref "U$2") (pin "5") (pinfunction "5_5") (pintype "passive"))
    )
    (net (code "87") (name "unconnected-(U$2-Pad15)") (class "Default")
      (node (ref "U$2") (pin "15") (pinfunction "15_15") (pintype "passive"))
    )
    (net (code "88") (name "unconnected-(U$3-Pad2)") (class "Default")
      (node (ref "U$3") (pin "2") (pinfunction "2_2") (pintype "passive"))
    )
    (net (code "89") (name "unconnected-(U$3-Pad3)") (class "Default")
      (node (ref "U$3") (pin "3") (pinfunction "3_3") (pintype "passive"))
    )
    (net (code "90") (name "unconnected-(U$3-Pad4)") (class "Default")
      (node (ref "U$3") (pin "4") (pinfunction "4_4") (pintype "passive"))
    )
    (net (code "91") (name "unconnected-(U$3-Pad5)") (class "Default")
      (node (ref "U$3") (pin "5") (pinfunction "5_5") (pintype "passive"))
    )
    (net (code "92") (name "unconnected-(U$3-Pad15)") (class "Default")
      (node (ref "U$3") (pin "15") (pinfunction "15_15") (pintype "passive"))
    )
    (net (code "93") (name "unconnected-(U$4-Pad2)") (class "Default")
      (node (ref "U$4") (pin "2") (pinfunction "2_2") (pintype "passive"))
    )
    (net (code "94") (name "unconnected-(U$4-Pad3)") (class "Default")
      (node (ref "U$4") (pin "3") (pinfunction "3_3") (pintype "passive"))
    )
    (net (code "95") (name "unconnected-(U$4-Pad4)") (class "Default")
      (node (ref "U$4") (pin "4") (pinfunction "4_4") (pintype "passive"))
    )
    (net (code "96") (name "unconnected-(U$4-Pad5)") (class "Default")
      (node (ref "U$4") (pin "5") (pinfunction "5_5") (pintype "passive"))
    )
    (net (code "97") (name "unconnected-(U$4-Pad15)") (class "Default")
      (node (ref "U$4") (pin "15") (pinfunction "15_15") (pintype "passive"))
    )
    (net (code "98") (name "unconnected-(U1-OUT-Pad2)") (class "Default")
      (node (ref "U1") (pin "2") (pinfunction "OUT_2") (pintype "output"))
    )
  )
)
